# Temp.net
KiCad netlist of a schematic drawn in Altium Designer
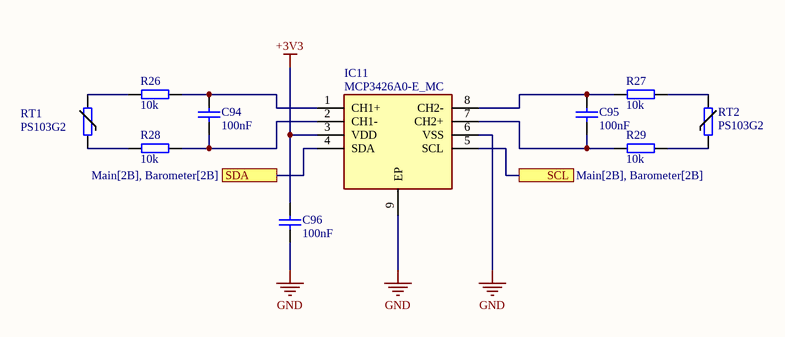
[diagram p0: Temp.SchDoc]

(export (version "E")
  (design (tool "Eeschema 10.0.6"))
  (components
    (comp (ref "C94")
      (value "100nF")
      (footprint "CAP0402")
      (fields
        (field (name "VOLTAGE") "50V")
        (field (name "MANUFACTURER_PART_NUMBER") "GRM155R71H104ME14D")
        (field (name "Comment") "Cap0402")
      )
      (libsource (lib "capacitorsSMD") (part "Cap0402"))
    )
    (comp (ref "C95")
      (value "100nF")
      (footprint "CAP0402")
      (fields
        (field (name "VOLTAGE") "50V")
        (field (name "MANUFACTURER_PART_NUMBER") "GRM155R71H104ME14D")
        (field (name "Comment") "Cap0402")
      )
      (libsource (lib "capacitorsSMD") (part "Cap0402"))
    )
    (comp (ref "C96")
      (value "100nF")
      (footprint "CAP0402")
      (fields
        (field (name "VOLTAGE") "50V")
        (field (name "MANUFACTURER_PART_NUMBER") "GRM155R71H104ME14D")
        (field (name "Comment") "Cap0402")
      )
      (libsource (lib "capacitorsSMD") (part "Cap0402"))
    )
    (comp (ref "IC11")
      (value "MCP3426A0-E_MC")
      (footprint "SamacSys:SON50P300X200X100-9N-D")
      (description "Integrated Circuit")
      (fields
        (field (name "MANUFACTURER_PART_NUMBER") "MCP3426A0-E/MC")
        (field (name "MOUSER PART NUMBER") "579-MCP3426A0E/MC")
      )
      (libsource (lib "*") (part "MCP3426A0-E_MC"))
    )
    (comp (ref "R26")
      (value "10k")
      (footprint "RES0402")
      (fields (field (name "MANUFACTURER_PART_NUMBER") "ERA-2AED103X") (field (name "Comment") "Res0402"))
      (libsource (lib "resistorSMD") (part "Res0402"))
    )
    (comp (ref "R27")
      (value "10k")
      (footprint "RES0402")
      (fields (field (name "MANUFACTURER_PART_NUMBER") "ERA-2AED103X") (field (name "Comment") "Res0402"))
      (libsource (lib "resistorSMD") (part "Res0402"))
    )
    (comp (ref "R28")
      (value "10k")
      (footprint "RES0402")
      (fields (field (name "MANUFACTURER_PART_NUMBER") "ERA-2AED103X") (field (name "Comment") "Res0402"))
      (libsource (lib "resistorSMD") (part "Res0402"))
    )
    (comp (ref "R29")
      (value "10k")
      (footprint "RES0402")
      (fields (field (name "MANUFACTURER_PART_NUMBER") "ERA-2AED103X") (field (name "Comment") "Res0402"))
      (libsource (lib "resistorSMD") (part "Res0402"))
    )
    (comp (ref "RT1")
      (value "PS103G2")
      (footprint "SamacSys:PS103G2")
      (description "Thermistor")
      (fields (field (name "MOUSER PART NUMBER") "803-PS103G2"))
      (libsource (lib "SamacSys") (part "PS103G2"))
    )
    (comp (ref "RT2")
      (value "PS103G2")
      (footprint "SamacSys:PS103G2")
      (description "Thermistor")
      (fields (field (name "MOUSER PART NUMBER") "803-PS103G2"))
      (libsource (lib "SamacSys") (part "PS103G2"))
    )
  )
  (nets
    (net (code "1") (name "+3V3") (class "Default")
      (node (ref "C96") (pin "2") (pinfunction "2_2") (pintype "passive"))
      (node (ref "IC11") (pin "3") (pinfunction "VDD_3") (pintype "passive"))
    )
    (net (code "2") (name "/SCL") (class "Default")
      (node (ref "IC11") (pin "5") (pinfunction "SCL_5") (pintype "passive"))
    )
    (net (code "3") (name "/SDA") (class "Default")
      (node (ref "IC11") (pin "4") (pinfunction "SDA_4") (pintype "passive"))
    )
    (net (code "4") (name "GND") (class "Default")
      (node (ref "C96") (pin "1") (pinfunction "1_1") (pintype "passive"))
      (node (ref "IC11") (pin "6") (pinfunction "VSS_6") (pintype "passive"))
      (node (ref "IC11") (pin "9") (pinfunction "EP_9") (pintype "passive"))
    )
    (net (code "5") (name "Net-(IC11-CH1+)") (class "Default")
      (node (ref "C94") (pin "2") (pinfunction "2_2") (pintype "passive"))
      (node (ref "IC11") (pin "1") (pinfunction "CH1+_1") (pintype "passive"))
      (node (ref "R26") (pin "1") (pinfunction "1_1") (pintype "passive"))
    )
    (net (code "6") (name "Net-(IC11-CH1-)") (class "Default")
      (node (ref "C94") (pin "1") (pinfunction "1_1") (pintype "passive"))
      (node (ref "IC11") (pin "2") (pinfunction "CH1-_2") (pintype "passive"))
      (node (ref "R28") (pin "1") (pinfunction "1_1") (pintype "passive"))
    )
    (net (code "7") (name "Net-(IC11-CH2+)") (class "Default")
      (node (ref "C95") (pin "1") (pinfunction "1_1") (pintype "passive"))
      (node (ref "IC11") (pin "7") (pinfunction "CH2+_7") (pintype "passive"))
      (node (ref "R29") (pin "1") (pinfunction "1_1") (pintype "passive"))
    )
    (net (code "8") (name "Net-(IC11-CH2-)") (class "Default")
      (node (ref "C95") (pin "2") (pinfunction "2_2") (pintype "passive"))
      (node (ref "IC11") (pin "8") (pinfunction "CH2-_8") (pintype "passive"))
      (node (ref "R27") (pin "1") (pinfunction "1_1") (pintype "passive"))
    )
    (net (code "9") (name "Net-(R26-Pad2)") (class "Default")
      (node (ref "R26") (pin "2") (pinfunction "2_2") (pintype "passive"))
      (node (ref "RT1") (pin "2") (pinfunction "2_2") (pintype "passive"))
    )
    (net (code "10") (name "Net-(R27-Pad2)") (class "Default")
      (node (ref "R27") (pin "2") (pinfunction "2_2") (pintype "passive"))
      (node (ref "RT2") (pin "2") (pinfunction "2_2") (pintype "passive"))
    )
    (net (code "11") (name "Net-(R28-Pad2)") (class "Default")
      (node (ref "R28") (pin "2") (pinfunction "2_2") (pintype "passive"))
      (node (ref "RT1") (pin "1") (pinfunction "1_1") (pintype "passive"))
    )
    (net (code "12") (name "Net-(R29-Pad2)") (class "Default")
      (node (ref "R29") (pin "2") (pinfunction "2_2") (pintype "passive"))
      (node (ref "RT2") (pin "1") (pinfunction "1_1") (pintype "passive"))
    )
  )
)
